# Connector.net
KiCad netlist of a schematic drawn in Altium Designer
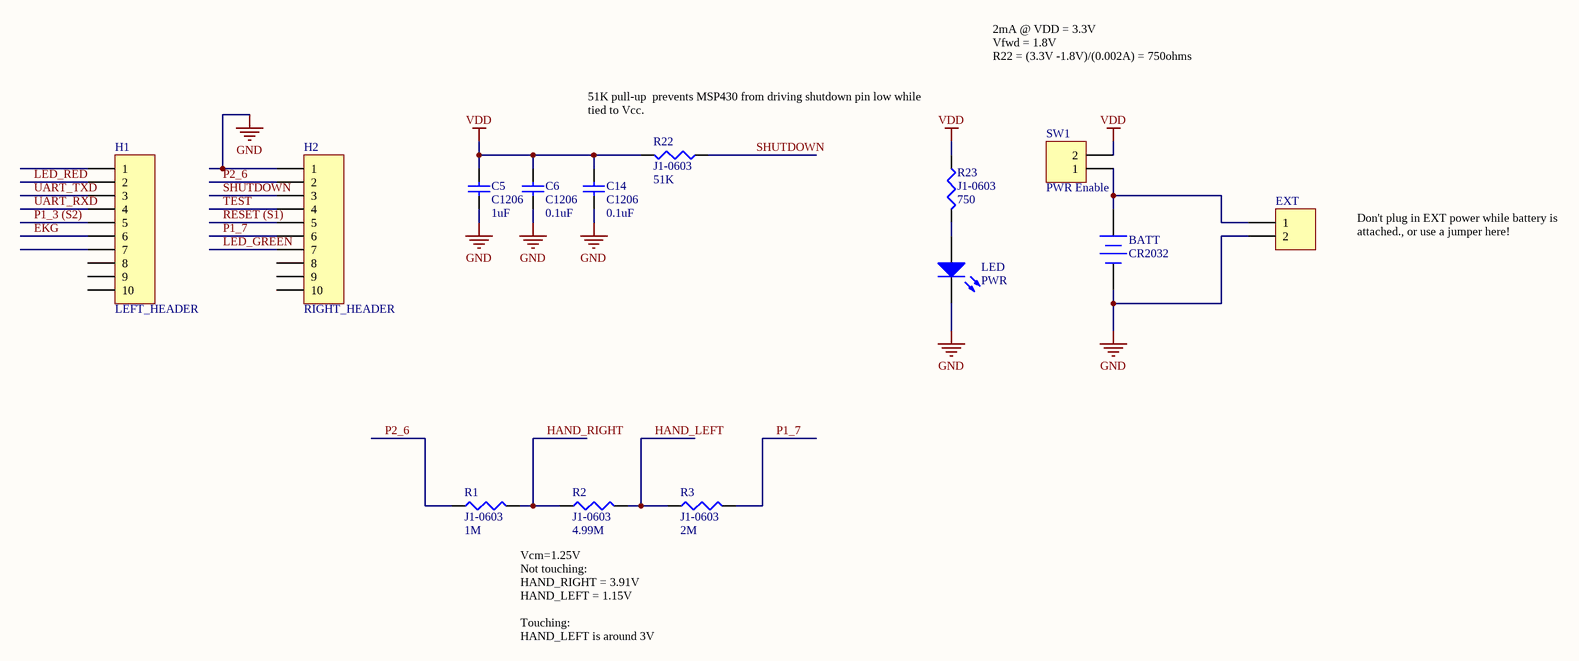
[diagram p0: Connector.SchDoc]

(export (version "E")
  (design (tool "Eeschema 10.0.6"))
  (components
    (comp (ref "BATT")
      (value "CR2032")
      (footprint "BAT_3003")
      (description "Multicell Battery")
      (fields (field (name "PUBLISHER") "Altium Limited"))
      (libsource (lib "Miscellaneous Devices") (part "Battery"))
    )
    (comp (ref "C5")
      (value "C1206")
      (footprint "C1206")
      (description "Capacitor (Semiconductor SIM Model)")
      (fields (field (name "ALTIUM_VALUE") "1uF") (field (name "PUBLISHER") "Altium Limited"))
      (libsource (lib "Miscellaneous Devices") (part "Cap Semi"))
    )
    (comp (ref "C6")
      (value "C1206")
      (footprint "C1206")
      (description "Capacitor (Semiconductor SIM Model)")
      (fields (field (name "ALTIUM_VALUE") "0.1uF") (field (name "PUBLISHER") "Altium Limited"))
      (libsource (lib "Miscellaneous Devices") (part "Cap Semi"))
    )
    (comp (ref "C14")
      (value "C1206")
      (footprint "C1206")
      (description "Capacitor (Semiconductor SIM Model)")
      (fields (field (name "ALTIUM_VALUE") "0.1uF") (field (name "PUBLISHER") "Altium Limited"))
      (libsource (lib "Miscellaneous Devices") (part "Cap Semi"))
    )
    (comp (ref "EXT")
      (value "~")
      (footprint "BAT-2")
      (description "Header, 2-Pin")
      (fields (field (name "PUBLISHER") "Altium Limited"))
      (libsource (lib "Miscellaneous Connectors") (part "Header 2"))
    )
    (comp (ref "H1")
      (value "LEFT_HEADER")
      (footprint "HDR1X10")
      (description "Header, 10-Pin")
      (fields (field (name "PUBLISHER") "Altium Limited"))
      (libsource (lib "Miscellaneous Connectors") (part "Header 10"))
    )
    (comp (ref "H2")
      (value "RIGHT_HEADER")
      (footprint "HDR1X10")
      (description "Header, 10-Pin")
      (fields (field (name "PUBLISHER") "Altium Limited"))
      (libsource (lib "Miscellaneous Connectors") (part "Header 10"))
    )
    (comp (ref "LED")
      (value "PWR")
      (footprint "RESC0603N")
      (description "RED LED")
      (fields (field (name "PUBLISHER") "Altium Limited"))
      (libsource (lib "Miscellaneous Devices") (part "LED2"))
    )
    (comp (ref "R1")
      (value "J1-0603")
      (footprint "RESC0603N")
      (description "Resistor")
      (fields (field (name "ALTIUM_VALUE") "1M") (field (name "PUBLISHER") "Altium Limited"))
      (libsource (lib "Miscellaneous Devices") (part "Res3"))
    )
    (comp (ref "R2")
      (value "J1-0603")
      (footprint "RESC0603N")
      (description "Resistor")
      (fields (field (name "ALTIUM_VALUE") "4.99M") (field (name "PUBLISHER") "Altium Limited"))
      (libsource (lib "Miscellaneous Devices") (part "Res3"))
    )
    (comp (ref "R3")
      (value "J1-0603")
      (footprint "RESC0603N")
      (description "Resistor")
      (fields (field (name "ALTIUM_VALUE") "2M") (field (name "PUBLISHER") "Altium Limited"))
      (libsource (lib "Miscellaneous Devices") (part "Res3"))
    )
    (comp (ref "R22")
      (value "J1-0603")
      (footprint "RESC0603N")
      (description "Resistor")
      (fields (field (name "ALTIUM_VALUE") "51K") (field (name "PUBLISHER") "Altium Limited"))
      (libsource (lib "Miscellaneous Devices") (part "Res3"))
    )
    (comp (ref "R23")
      (value "J1-0603")
      (footprint "RESC0603N")
      (description "Resistor")
      (fields (field (name "ALTIUM_VALUE") "750") (field (name "PUBLISHER") "Altium Limited"))
      (libsource (lib "Miscellaneous Devices") (part "Res3"))
    )
    (comp (ref "SW1")
      (value "PWR Enable")
      (footprint "HDR1X2")
      (description "Header, 2-Pin")
      (fields (field (name "PUBLISHER") "Altium Limited"))
      (libsource (lib "") (part "Header 2_1"))
    )
  )
  (nets
    (net (code "1") (name "/EKG") (class "Default")
      (node (ref "H1") (pin "6") (pinfunction "6_6") (pintype "passive"))
    )
    (net (code "2") (name "/HAND_LEFT") (class "Default")
      (node (ref "R2") (pin "2") (pinfunction "2_2") (pintype "passive"))
      (node (ref "R3") (pin "1") (pinfunction "1_1") (pintype "passive"))
    )
    (net (code "3") (name "/HAND_RIGHT") (class "Default")
      (node (ref "R1") (pin "2") (pinfunction "2_2") (pintype "passive"))
      (node (ref "R2") (pin "1") (pinfunction "1_1") (pintype "passive"))
    )
    (net (code "4") (name "/LED_GREEN") (class "Default")
      (node (ref "H2") (pin "7") (pinfunction "7_7") (pintype "passive"))
    )
    (net (code "5") (name "/LED_RED") (class "Default")
      (node (ref "H1") (pin "2") (pinfunction "2_2") (pintype "passive"))
    )
    (net (code "6") (name "/P1_3 (S2)") (class "Default")
      (node (ref "H1") (pin "5") (pinfunction "5_5") (pintype "passive"))
    )
    (net (code "7") (name "/P1_7") (class "Default")
      (node (ref "H2") (pin "6") (pinfunction "6_6") (pintype "passive"))
      (node (ref "R3") (pin "2") (pinfunction "2_2") (pintype "passive"))
    )
    (net (code "8") (name "/P2_6") (class "Default")
      (node (ref "H2") (pin "2") (pinfunction "2_2") (pintype "passive"))
      (node (ref "R1") (pin "1") (pinfunction "1_1") (pintype "passive"))
    )
    (net (code "9") (name "/RESET (S1)") (class "Default")
      (node (ref "H2") (pin "5") (pinfunction "5_5") (pintype "passive"))
    )
    (net (code "10") (name "/SHUTDOWN") (class "Default")
      (node (ref "H2") (pin "3") (pinfunction "3_3") (pintype "passive"))
      (node (ref "R22") (pin "1") (pinfunction "1_1") (pintype "passive"))
    )
    (net (code "11") (name "/TEST") (class "Default")
      (node (ref "H2") (pin "4") (pinfunction "4_4") (pintype "passive"))
    )
    (net (code "12") (name "/UART_RXD") (class "Default")
      (node (ref "H1") (pin "4") (pinfunction "4_4") (pintype "passive"))
    )
    (net (code "13") (name "/UART_TXD") (class "Default")
      (node (ref "H1") (pin "3") (pinfunction "3_3") (pintype "passive"))
    )
    (net (code "14") (name "GND") (class "Default")
      (node (ref "BATT") (pin "2") (pinfunction "-_2") (pintype "passive"))
      (node (ref "C14") (pin "1") (pinfunction "1_1") (pintype "passive"))
      (node (ref "C5") (pin "1") (pinfunction "1_1") (pintype "passive"))
      (node (ref "C6") (pin "1") (pinfunction "1_1") (pintype "passive"))
      (node (ref "EXT") (pin "2") (pinfunction "2_2") (pintype "passive"))
      (node (ref "H2") (pin "1") (pinfunction "1_1") (pintype "passive"))
      (node (ref "LED") (pin "2") (pinfunction "K_2") (pintype "passive"))
    )
    (net (code "15") (name "Net-(BATT-+)") (class "Default")
      (node (ref "BATT") (pin "1") (pinfunction "+_1") (pintype "passive"))
      (node (ref "EXT") (pin "1") (pinfunction "1_1") (pintype "passive"))
      (node (ref "SW1") (pin "1") (pinfunction "1_1") (pintype "passive"))
    )
    (net (code "16") (name "Net-(LED-A)") (class "Default")
      (node (ref "LED") (pin "1") (pinfunction "A_1") (pintype "passive"))
      (node (ref "R23") (pin "2") (pinfunction "2_2") (pintype "passive"))
    )
    (net (code "17") (name "VDD") (class "Default")
      (node (ref "C14") (pin "2") (pinfunction "2_2") (pintype "passive"))
      (node (ref "C5") (pin "2") (pinfunction "2_2") (pintype "passive"))
      (node (ref "C6") (pin "2") (pinfunction "2_2") (pintype "passive"))
      (node (ref "R22") (pin "2") (pinfunction "2_2") (pintype "passive"))
      (node (ref "R23") (pin "1") (pinfunction "1_1") (pintype "passive"))
      (node (ref "SW1") (pin "2") (pinfunction "2_2") (pintype "passive"))
    )
    (net (code "18") (name "unconnected-(H1-Pad1)") (class "Default")
      (node (ref "H1") (pin "1") (pinfunction "1_1") (pintype "passive"))
    )
    (net (code "19") (name "unconnected-(H1-Pad7)") (class "Default")
      (node (ref "H1") (pin "7") (pinfunction "7_7") (pintype "passive"))
    )
    (net (code "20") (name "unconnected-(H1-Pad8)") (class "Default")
      (node (ref "H1") (pin "8") (pinfunction "8_8") (pintype "passive"))
    )
    (net (code "21") (name "unconnected-(H1-Pad9)") (class "Default")
      (node (ref "H1") (pin "9") (pinfunction "9_9") (pintype "passive"))
    )
    (net (code "22") (name "unconnected-(H1-Pad10)") (class "Default")
      (node (ref "H1") (pin "10") (pinfunction "10_10") (pintype "passive"))
    )
    (net (code "23") (name "unconnected-(H2-Pad8)") (class "Default")
      (node (ref "H2") (pin "8") (pinfunction "8_8") (pintype "passive"))
    )
    (net (code "24") (name "unconnected-(H2-Pad9)") (class "Default")
      (node (ref "H2") (pin "9") (pinfunction "9_9") (pintype "passive"))
    )
    (net (code "25") (name "unconnected-(H2-Pad10)") (class "Default")
      (node (ref "H2") (pin "10") (pinfunction "10_10") (pintype "passive"))
    )
  )
)
